# Principal_Node.net
KiCad netlist of a schematic drawn in Altium Designer
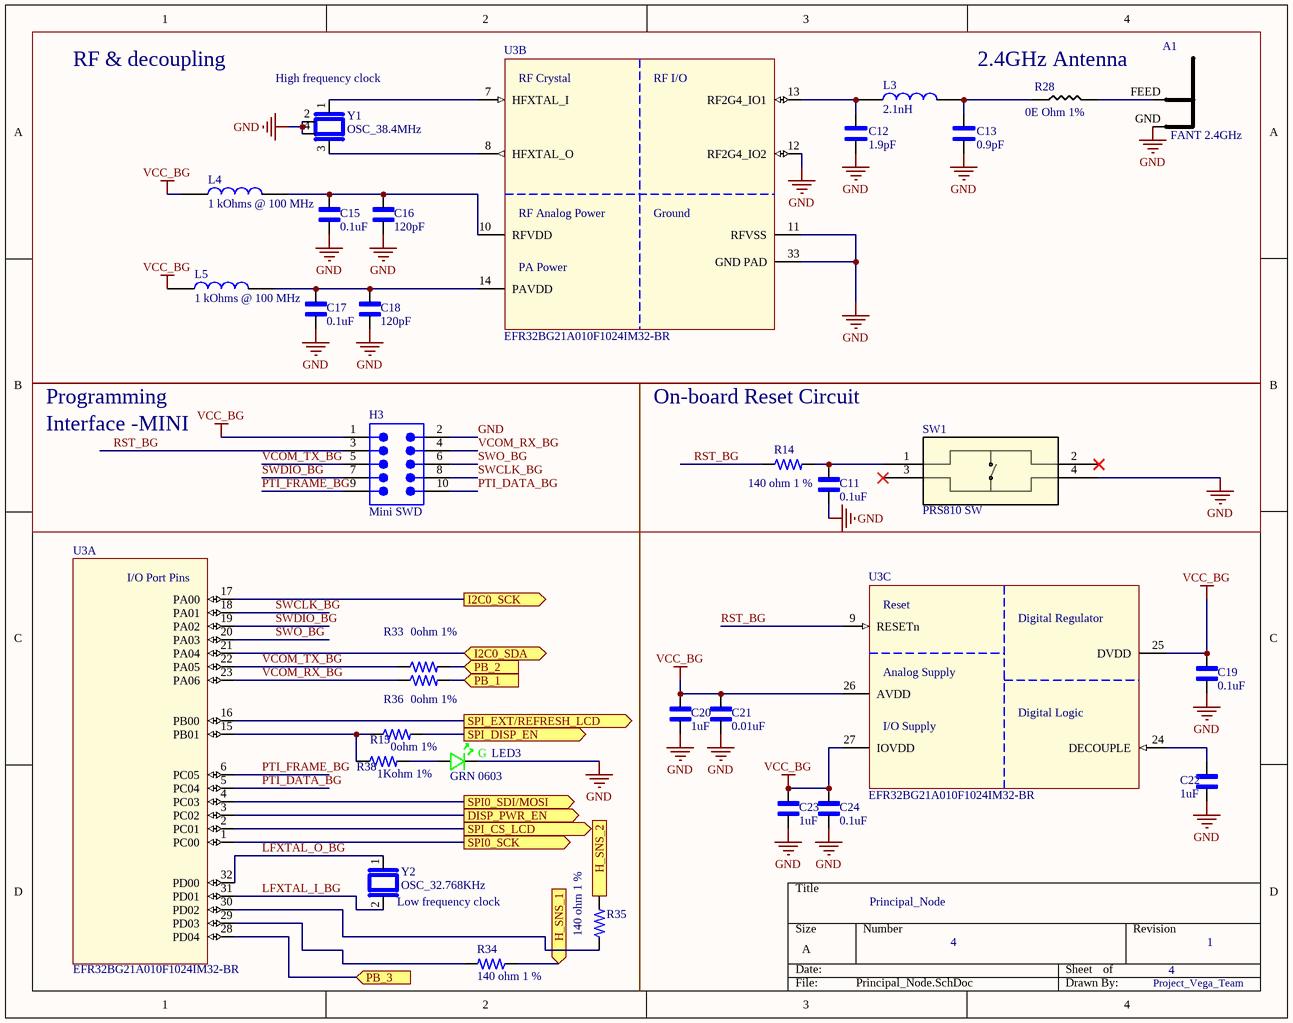
[diagram p0: Principal_Node.SchDoc]

(export (version "E")
  (design (tool "Eeschema 10.0.6"))
  (components
    (comp (ref "A1")
      (value "FANT 2.4GHz")
      (footprint "FANT_2P4")
      (description "Inverted F antenna")
      (libsource (lib "Project_Vega") (part "FANT_2P4"))
    )
    (comp (ref "C11")
      (value "0.1uF")
      (footprint "CAPC1608X90")
      (description "0.1 ÂµF Â±10% 50V Ceramic Capacitor X7R 0603 (1608 Metric)")
      (fields (field (name "MF") "Yageo") (field (name "MP") "CC0603KRX7R9BB104"))
      (libsource (lib "Project_Vega") (part "CC0603KRX7R9BB104"))
    )
    (comp (ref "C12")
      (value "1.9pF")
      (footprint "0402_Passive_Capacitor")
      (description "MULTILAYER CERAMIC CAPACITORS MLCC - SMD/SMT 1UF 25V 0402 ROHS")
      (fields (field (name "MFR PART #") "CL05A105KA5NQNC") (field (name "LCSC PART#") "C52923"))
      (libsource (lib "Project_Vega") (part "C_0402"))
    )
    (comp (ref "C13")
      (value "0.9pF")
      (footprint "0402_Passive_Capacitor")
      (description "MULTILAYER CERAMIC CAPACITORS MLCC - SMD/SMT 1UF 25V 0402 ROHS")
      (fields (field (name "MFR PART #") "CL05A105KA5NQNC") (field (name "LCSC PART#") "C52923"))
      (libsource (lib "Project_Vega") (part "C_0402"))
    )
    (comp (ref "C15")
      (value "0.1uF")
      (footprint "CAPC1608X90")
      (description "0.1 ÂµF Â±10% 50V Ceramic Capacitor X7R 0603 (1608 Metric)")
      (fields (field (name "MF") "Yageo") (field (name "MP") "CC0603KRX7R9BB104"))
      (libsource (lib "Project_Vega") (part "CC0603KRX7R9BB104"))
    )
    (comp (ref "C16")
      (value "120pF")
      (footprint "CAPC1608X90")
      (description "0.1 ÂµF Â±10% 50V Ceramic Capacitor X7R 0603 (1608 Metric)")
      (fields (field (name "MF") "Yageo") (field (name "MP") "CC0603KRX7R9BB104"))
      (libsource (lib "Project_Vega") (part "CC0603KRX7R9BB104"))
    )
    (comp (ref "C17")
      (value "0.1uF")
      (footprint "CAPC1608X90")
      (description "0.1 ÂµF Â±10% 50V Ceramic Capacitor X7R 0603 (1608 Metric)")
      (fields (field (name "MF") "Yageo") (field (name "MP") "CC0603KRX7R9BB104"))
      (libsource (lib "Project_Vega") (part "CC0603KRX7R9BB104"))
    )
    (comp (ref "C18")
      (value "120pF")
      (footprint "CAPC1608X90")
      (description "0.1 ÂµF Â±10% 50V Ceramic Capacitor X7R 0603 (1608 Metric)")
      (fields (field (name "MF") "Yageo") (field (name "MP") "CC0603KRX7R9BB104"))
      (libsource (lib "Project_Vega") (part "CC0603KRX7R9BB104"))
    )
    (comp (ref "C19")
      (value "0.1uF")
      (footprint "CAPC1608X90")
      (description "0.1 ÂµF Â±10% 50V Ceramic Capacitor X7R 0603 (1608 Metric)")
      (fields (field (name "MF") "Yageo") (field (name "MP") "CC0603KRX7R9BB104"))
      (libsource (lib "Project_Vega") (part "CC0603KRX7R9BB104"))
    )
    (comp (ref "C20")
      (value "1uF")
      (footprint "CAPC1608X90")
      (description "0.1 ÂµF Â±10% 50V Ceramic Capacitor X7R 0603 (1608 Metric)")
      (fields (field (name "MF") "Yageo") (field (name "MP") "CC0603KRX7R9BB104"))
      (libsource (lib "Project_Vega") (part "CC0603KRX7R9BB104"))
    )
    (comp (ref "C21")
      (value "0.01uF")
      (footprint "CAPC1608X90")
      (description "0.1 ÂµF Â±10% 50V Ceramic Capacitor X7R 0603 (1608 Metric)")
      (fields (field (name "MF") "Yageo") (field (name "MP") "CC0603KRX7R9BB104"))
      (libsource (lib "Project_Vega") (part "CC0603KRX7R9BB104"))
    )
    (comp (ref "C22")
      (value "1uF")
      (footprint "CAPC1608X90")
      (description "0.1 ÂµF Â±10% 50V Ceramic Capacitor X7R 0603 (1608 Metric)")
      (fields (field (name "MF") "Yageo") (field (name "MP") "CC0603KRX7R9BB104"))
      (libsource (lib "Project_Vega") (part "CC0603KRX7R9BB104"))
    )
    (comp (ref "C23")
      (value "1uF")
      (footprint "CAPC1608X90")
      (description "0.1 ÂµF Â±10% 50V Ceramic Capacitor X7R 0603 (1608 Metric)")
      (fields (field (name "MF") "Yageo") (field (name "MP") "CC0603KRX7R9BB104"))
      (libsource (lib "Project_Vega") (part "CC0603KRX7R9BB104"))
    )
    (comp (ref "C24")
      (value "0.1uF")
      (footprint "CAPC1608X90")
      (description "0.1 ÂµF Â±10% 50V Ceramic Capacitor X7R 0603 (1608 Metric)")
      (fields (field (name "MF") "Yageo") (field (name "MP") "CC0603KRX7R9BB104"))
      (libsource (lib "Project_Vega") (part "CC0603KRX7R9BB104"))
    )
    (comp (ref "H3")
      (value "Mini SWD")
      (footprint "FTSH-105-01-XXX-DV-K")
      (description "Mini SWD 0.05 Pitch Connector - 10 Pin SMT Box Header ¦ Adafruit Industries 4048")
      (fields
        (field (name "MANUFACTURER") "Adafruit Industries")
        (field (name "MANUFACTURER PART NUMBER") "4048")
      )
      (libsource (lib "Project_Vega") (part "Debug Connector Mini SWD - 0.05{dblquote}"))
    )
    (comp (ref "L3")
      (value "2.1nH")
      (footprint "0402_Inductor")
      (description "Inductor Package 0603")
      (fields (field (name "MP") "LQM18DN100M70L") (field (name "MF") "Murata Electronics"))
      (libsource (lib "Project_Vega") (part "IND_0402"))
    )
    (comp (ref "L4")
      (value "1 kOhms @ 100 MHz")
      (footprint "INDC1608X95N")
      (description "Inductor with Inductance 10uH Tol.+/-20% Package 0603 (1608)")
      (fields (field (name "MP") "LQM18DN100M70L") (field (name "MF") "Murata Electronics"))
      (libsource (lib "Project_Vega") (part "LQM18DN100M70L"))
    )
    (comp (ref "L5")
      (value "1 kOhms @ 100 MHz")
      (footprint "INDC1608X95N")
      (description "Inductor with Inductance 10uH Tol.+/-20% Package 0603 (1608)")
      (fields (field (name "MP") "LQM18DN100M70L") (field (name "MF") "Murata Electronics"))
      (libsource (lib "Project_Vega") (part "LQM18DN100M70L"))
    )
    (comp (ref "LED3")
      (value "GRN 0603")
      (footprint "LED_0603_GRN_WL-SMCW")
      (description "LED, 0603, GREEN, 430MCD, 520NM")
      (fields
        (field (name "MANUFACTURER") "Wurth Electronics")
        (field (name "MANUFACTURER PART NUMBER") "150060GS75000")
      )
      (libsource (lib "Project_Vega") (part "LED_green"))
    )
    (comp (ref "R14")
      (value "140 ohm 1 %")
      (footprint "RES_0603_1608X06")
      (description "SMD Chip Resistor, 140 Ohm, ± 1%, 100 mW, 0603 [1608 Metric], Thick Film, General Purpose")
      (fields
        (field (name "MANUFACTURER") "Yageo")
        (field (name "MANUFACTURER PART NUMBER") "RC0603FR-07140RL")
      )
      (libsource (lib "Project_Vega") (part "RC0603FR-07140RL"))
    )
    (comp (ref "R15")
      (value "0ohm 1%")
      (footprint "RES_0603")
      (description "Thick film general purpose resistor 0603")
      (fields (field (name "MP") "RC0603JR-070RL"))
      (libsource (lib "Project_Vega") (part "RES_0603"))
    )
    (comp (ref "R28")
      (value "0E Ohm 1%")
      (footprint "0402_Passive_Resistor")
      (description "CHIP RESISTOR - SURFACE MOUNT 0OHMS ±1% 1/16W 0402 ROHS")
      (fields (field (name "MFR PART #") "0402WGF0000TCE") (field (name "LCSC PART#") "C17168"))
      (libsource (lib "Project_Vega") (part "R_0Ohm_0402"))
    )
    (comp (ref "R33")
      (value "0ohm 1%")
      (footprint "RES_0603")
      (description "Thick film general purpose resistor 0603")
      (fields (field (name "MP") "RC0603JR-070RL"))
      (libsource (lib "Project_Vega") (part "RES_0603"))
    )
    (comp (ref "R34")
      (value "140 ohm 1 %")
      (footprint "RES_0603_1608X06")
      (description "SMD Chip Resistor, 140 Ohm, ± 1%, 100 mW, 0603 [1608 Metric], Thick Film, General Purpose")
      (fields
        (field (name "MANUFACTURER") "Yageo")
        (field (name "MANUFACTURER PART NUMBER") "RC0603FR-07140RL")
      )
      (libsource (lib "Project_Vega") (part "RC0603FR-07140RL"))
    )
    (comp (ref "R35")
      (value "140 ohm 1 %")
      (footprint "RES_0603_1608X06")
      (description "SMD Chip Resistor, 140 Ohm, ± 1%, 100 mW, 0603 [1608 Metric], Thick Film, General Purpose")
      (fields
        (field (name "MANUFACTURER") "Yageo")
        (field (name "MANUFACTURER PART NUMBER") "RC0603FR-07140RL")
      )
      (libsource (lib "Project_Vega") (part "RC0603FR-07140RL"))
    )
    (comp (ref "R36")
      (value "0ohm 1%")
      (footprint "RES_0603")
      (description "Thick film general purpose resistor 0603")
      (fields (field (name "MP") "RC0603JR-070RL"))
      (libsource (lib "Project_Vega") (part "RES_0603"))
    )
    (comp (ref "R38")
      (value "1Kohm 1%")
      (footprint "RES_0603")
      (description "Thick film general purpose resistor 0603")
      (fields (field (name "MP") "RC0603JR-070RL"))
      (libsource (lib "Project_Vega") (part "RES_0603"))
    )
    (comp (ref "SW1")
      (value "PRS810 SW")
      (footprint "PTS810_CNK")
      (description "Switch Tactile N.O. SPST Button J-Bend 0.05A 16V 150000Cycles 1.569N SMD T/R")
      (fields
        (field (name "MANUFACTURER") "ITT C&K")
        (field (name "MANUFACTURER PART NUMBER") "PTS810SJM250SMTRLFS")
      )
      (libsource (lib "Project_Vega") (part "PTS810SJM250SMTRLFS"))
    )
    (comp (ref "U3")
      (value "EFR32BG21A010F1024IM32-BR")
      (footprint "QFN32-EFR32xG2xIM32-BR")
      (description "Blue Gecko, QFN32, 2.4G, 10dB, Bluetooth 5.1, 1024kB, 96kB(RAM), 20 GPIO")
      (fields (field (name "MANUFACTURER") "Silicon Labs"))
      (libsource (lib "Project_Vega") (part "EFR32BG21A010F1024IM32-BR"))
    )
    (comp (ref "Y1")
      (value "OSC_38.4MHz")
      (footprint "OSC_38.4MHz")
      (description "38.4 MHz ±10ppm Crystal 10pF 40 Ohms 4-SMD, No Lead")
      (fields
        (field (name "MF") "{'manufacturer': u'Murata Electronics'}")
        (field (name "MP") "XRCGB38M400F2P00R0")
      )
      (libsource (lib "Project_Vega") (part "OSC_38.4MHz"))
    )
    (comp (ref "Y2")
      (value "OSC_32.768KHz")
      (footprint "OSC_32.768KHz")
      (description "Tuning Fork Crystal 32.768kHz in 1.2 x 2.0mm package")
      (fields (field (name "MF") "Micro Crystal") (field (name "MP") "CM8V-T1A-32.768KHZ-7PF-20PPM-TA-QC"))
      (libsource (lib "Project_Vega") (part "OSC_32.768KHz"))
    )
  )
  (nets
    (net (code "1") (name "/DISP_PWR_EN") (class "Default")
      (node (ref "U3") (pin "3") (pinfunction "PC02_3") (pintype "bidirectional"))
    )
    (net (code "2") (name "/H_SNS_1") (class "Default")
      (node (ref "R34") (pin "1") (pinfunction "1_1") (pintype "passive"))
    )
    (net (code "3") (name "/H_SNS_2") (class "Default")
      (node (ref "R35") (pin "2") (pinfunction "2_2") (pintype "passive"))
    )
    (net (code "4") (name "/I2C0_SCK") (class "Default")
      (node (ref "U3") (pin "17") (pinfunction "PA00_17") (pintype "bidirectional"))
    )
    (net (code "5") (name "/I2C0_SDA") (class "Default")
      (node (ref "U3") (pin "21") (pinfunction "PA04_21") (pintype "bidirectional"))
    )
    (net (code "6") (name "/LFXTAL_I_BG") (class "Default")
      (node (ref "U3") (pin "31") (pinfunction "PD01_31") (pintype "bidirectional"))
      (node (ref "Y2") (pin "2") (pinfunction "2_2") (pintype "passive"))
    )
    (net (code "7") (name "/LFXTAL_O_BG") (class "Default")
      (node (ref "U3") (pin "32") (pinfunction "PD00_32") (pintype "bidirectional"))
      (node (ref "Y2") (pin "1") (pinfunction "1_1") (pintype "passive"))
    )
    (net (code "8") (name "/PB_1") (class "Default")
      (node (ref "R36") (pin "2") (pinfunction "2_2") (pintype "passive"))
    )
    (net (code "9") (name "/PB_2") (class "Default")
      (node (ref "R33") (pin "2") (pinfunction "2_2") (pintype "passive"))
    )
    (net (code "10") (name "/PB_3") (class "Default")
      (node (ref "U3") (pin "28") (pinfunction "PD04_28") (pintype "bidirectional"))
    )
    (net (code "11") (name "/PTI_DATA_BG") (class "Default")
      (node (ref "H3") (pin "10") (pinfunction "10_10") (pintype "passive"))
      (node (ref "U3") (pin "5") (pinfunction "PC04_5") (pintype "bidirectional"))
    )
    (net (code "12") (name "/PTI_FRAME_BG") (class "Default")
      (node (ref "H3") (pin "9") (pinfunction "9_9") (pintype "passive"))
      (node (ref "U3") (pin "6") (pinfunction "PC05_6") (pintype "bidirectional"))
    )
    (net (code "13") (name "/RST_BG") (class "Default")
      (node (ref "H3") (pin "3") (pinfunction "3_3") (pintype "passive"))
      (node (ref "R14") (pin "1") (pinfunction "1_1") (pintype "passive"))
      (node (ref "U3") (pin "9") (pinfunction "RESETn_9") (pintype "input"))
    )
    (net (code "14") (name "/SPI0_SCK") (class "Default")
      (node (ref "U3") (pin "1") (pinfunction "PC00_1") (pintype "bidirectional"))
    )
    (net (code "15") (name "/SPI0_SDI{slash}MOSI") (class "Default")
      (node (ref "U3") (pin "4") (pinfunction "PC03_4") (pintype "bidirectional"))
    )
    (net (code "16") (name "/SPI_CS_LCD") (class "Default")
      (node (ref "U3") (pin "2") (pinfunction "PC01_2") (pintype "bidirectional"))
    )
    (net (code "17") (name "/SPI_DISP_EN") (class "Default")
      (node (ref "R15") (pin "2") (pinfunction "2_2") (pintype "passive"))
    )
    (net (code "18") (name "/SPI_EXT{slash}REFRESH_LCD") (class "Default")
      (node (ref "U3") (pin "16") (pinfunction "PB00_16") (pintype "bidirectional"))
    )
    (net (code "19") (name "/SWCLK_BG") (class "Default")
      (node (ref "H3") (pin "8") (pinfunction "8_8") (pintype "passive"))
      (node (ref "U3") (pin "18") (pinfunction "PA01_18") (pintype "bidirectional"))
    )
    (net (code "20") (name "/SWDIO_BG") (class "Default")
      (node (ref "H3") (pin "7") (pinfunction "7_7") (pintype "passive"))
      (node (ref "U3") (pin "19") (pinfunction "PA02_19") (pintype "bidirectional"))
    )
    (net (code "21") (name "/SWO_BG") (class "Default")
      (node (ref "H3") (pin "6") (pinfunction "6_6") (pintype "passive"))
      (node (ref "U3") (pin "20") (pinfunction "PA03_20") (pintype "bidirectional"))
    )
    (net (code "22") (name "/VCOM_RX_BG") (class "Default")
      (node (ref "H3") (pin "4") (pinfunction "4_4") (pintype "passive"))
      (node (ref "R36") (pin "1") (pinfunction "1_1") (pintype "passive"))
      (node (ref "U3") (pin "23") (pinfunction "PA06_23") (pintype "bidirectional"))
    )
    (net (code "23") (name "/VCOM_TX_BG") (class "Default")
      (node (ref "H3") (pin "5") (pinfunction "5_5") (pintype "passive"))
      (node (ref "R33") (pin "1") (pinfunction "1_1") (pintype "passive"))
      (node (ref "U3") (pin "22") (pinfunction "PA05_22") (pintype "bidirectional"))
    )
    (net (code "24") (name "GND") (class "Default")
      (node (ref "A1") (pin "GND") (pinfunction "6_GND") (pintype "passive"))
      (node (ref "C11") (pin "2") (pinfunction "2_2") (pintype "passive"))
      (node (ref "C12") (pin "2") (pinfunction "2_2") (pintype "passive"))
      (node (ref "C13") (pin "2") (pinfunction "2_2") (pintype "passive"))
      (node (ref "C15") (pin "2") (pinfunction "2_2") (pintype "passive"))
      (node (ref "C16") (pin "2") (pinfunction "2_2") (pintype "passive"))
      (node (ref "C17") (pin "2") (pinfunction "2_2") (pintype "passive"))
      (node (ref "C18") (pin "2") (pinfunction "2_2") (pintype "passive"))
      (node (ref "C19") (pin "2") (pinfunction "2_2") (pintype "passive"))
      (node (ref "C20") (pin "2") (pinfunction "2_2") (pintype "passive"))
      (node (ref "C21") (pin "2") (pinfunction "2_2") (pintype "passive"))
      (node (ref "C22") (pin "2") (pinfunction "2_2") (pintype "passive"))
      (node (ref "C23") (pin "2") (pinfunction "2_2") (pintype "passive"))
      (node (ref "C24") (pin "2") (pinfunction "2_2") (pintype "passive"))
      (node (ref "H3") (pin "2") (pinfunction "2_2") (pintype "passive"))
      (node (ref "LED3") (pin "C") (pinfunction "C_C") (pintype "passive"))
      (node (ref "SW1") (pin "4") (pinfunction "4_4") (pintype "passive"))
      (node (ref "U3") (pin "11") (pinfunction "RFVSS_11") (pintype "power_in"))
      (node (ref "U3") (pin "12") (pinfunction "RF2G4_IO2_12") (pintype "bidirectional"))
      (node (ref "U3") (pin "33") (pinfunction "GND_PAD_33") (pintype "power_in"))
      (node (ref "Y1") (pin "2") (pinfunction "2_2") (pintype "passive"))
      (node (ref "Y1") (pin "4") (pinfunction "4_4") (pintype "passive"))
    )
    (net (code "25") (name "Net-(A1-6-PadFEED)") (class "Default")
      (node (ref "A1") (pin "FEED") (pinfunction "6_FEED") (pintype "passive"))
      (node (ref "R28") (pin "2") (pinfunction "2_2") (pintype "passive"))
    )
    (net (code "26") (name "Net-(C11-Pad1)") (class "Default")
      (node (ref "C11") (pin "1") (pinfunction "1_1") (pintype "passive"))
      (node (ref "R14") (pin "2") (pinfunction "2_2") (pintype "passive"))
      (node (ref "SW1") (pin "1") (pinfunction "1_1") (pintype "passive"))
    )
    (net (code "27") (name "Net-(C13-Pad1)") (class "Default")
      (node (ref "C13") (pin "1") (pinfunction "1_1") (pintype "passive"))
      (node (ref "L3") (pin "2") (pinfunction "2_2") (pintype "passive"))
      (node (ref "R28") (pin "1") (pinfunction "1_1") (pintype "passive"))
    )
    (net (code "28") (name "Net-(LED3-PadA)") (class "Default")
      (node (ref "LED3") (pin "A") (pinfunction "A_A") (pintype "passive"))
      (node (ref "R38") (pin "2") (pinfunction "2_2") (pintype "passive"))
    )
    (net (code "29") (name "Net-(U3A-PB01)") (class "Default")
      (node (ref "R15") (pin "1") (pinfunction "1_1") (pintype "passive"))
      (node (ref "R38") (pin "1") (pinfunction "1_1") (pintype "passive"))
      (node (ref "U3") (pin "15") (pinfunction "PB01_15") (pintype "bidirectional"))
    )
    (net (code "30") (name "Net-(U3A-PD02)") (class "Default")
      (node (ref "R35") (pin "1") (pinfunction "1_1") (pintype "passive"))
      (node (ref "U3") (pin "30") (pinfunction "PD02_30") (pintype "bidirectional"))
    )
    (net (code "31") (name "Net-(U3A-PD03)") (class "Default")
      (node (ref "R34") (pin "2") (pinfunction "2_2") (pintype "passive"))
      (node (ref "U3") (pin "29") (pinfunction "PD03_29") (pintype "bidirectional"))
    )
    (net (code "32") (name "Net-(U3B-HFXTAL_I)") (class "Default")
      (node (ref "U3") (pin "7") (pinfunction "HFXTAL_I_7") (pintype "input"))
      (node (ref "Y1") (pin "1") (pinfunction "1_1") (pintype "passive"))
    )
    (net (code "33") (name "Net-(U3B-HFXTAL_O)") (class "Default")
      (node (ref "U3") (pin "8") (pinfunction "HFXTAL_O_8") (pintype "output"))
      (node (ref "Y1") (pin "3") (pinfunction "3_3") (pintype "passive"))
    )
    (net (code "34") (name "Net-(U3B-PAVDD)") (class "Default")
      (node (ref "C17") (pin "1") (pinfunction "1_1") (pintype "passive"))
      (node (ref "C18") (pin "1") (pinfunction "1_1") (pintype "passive"))
      (node (ref "L5") (pin "2") (pinfunction "2_2") (pintype "passive"))
      (node (ref "U3") (pin "14") (pinfunction "PAVDD_14") (pintype "power_in"))
    )
    (net (code "35") (name "Net-(U3B-RF2G4_IO1)") (class "Default")
      (node (ref "C12") (pin "1") (pinfunction "1_1") (pintype "passive"))
      (node (ref "L3") (pin "1") (pinfunction "1_1") (pintype "passive"))
      (node (ref "U3") (pin "13") (pinfunction "RF2G4_IO1_13") (pintype "bidirectional"))
    )
    (net (code "36") (name "Net-(U3B-RFVDD)") (class "Default")
      (node (ref "C15") (pin "1") (pinfunction "1_1") (pintype "passive"))
      (node (ref "C16") (pin "1") (pinfunction "1_1") (pintype "passive"))
      (node (ref "L4") (pin "2") (pinfunction "2_2") (pintype "passive"))
      (node (ref "U3") (pin "10") (pinfunction "RFVDD_10") (pintype "power_in"))
    )
    (net (code "37") (name "Net-(U3C-DECOUPLE)") (class "Default")
      (node (ref "C22") (pin "1") (pinfunction "1_1") (pintype "passive"))
      (node (ref "U3") (pin "24") (pinfunction "DECOUPLE_24") (pintype "input"))
    )
    (net (code "38") (name "VCC_BG") (class "Default")
      (node (ref "C19") (pin "1") (pinfunction "1_1") (pintype "passive"))
      (node (ref "C20") (pin "1") (pinfunction "1_1") (pintype "passive"))
      (node (ref "C21") (pin "1") (pinfunction "1_1") (pintype "passive"))
      (node (ref "C23") (pin "1") (pinfunction "1_1") (pintype "passive"))
      (node (ref "C24") (pin "1") (pinfunction "1_1") (pintype "passive"))
      (node (ref "H3") (pin "1") (pinfunction "1_1") (pintype "passive"))
      (node (ref "L4") (pin "1") (pinfunction "1_1") (pintype "passive"))
      (node (ref "L5") (pin "1") (pinfunction "1_1") (pintype "passive"))
      (node (ref "U3") (pin "25") (pinfunction "DVDD_25") (pintype "power_in"))
      (node (ref "U3") (pin "26") (pinfunction "AVDD_26") (pintype "power_in"))
      (node (ref "U3") (pin "27") (pinfunction "IOVDD_27") (pintype "power_in"))
    )
    (net (code "39") (name "unconnected-(SW1-Pad2)") (class "Default")
      (node (ref "SW1") (pin "2") (pinfunction "2_2") (pintype "passive+no_connect"))
    )
    (net (code "40") (name "unconnected-(SW1-Pad3)") (class "Default")
      (node (ref "SW1") (pin "3") (pinfunction "3_3") (pintype "passive+no_connect"))
    )
  )
)
